# CurrentSensor.net
KiCad netlist of a schematic drawn in EAGLE
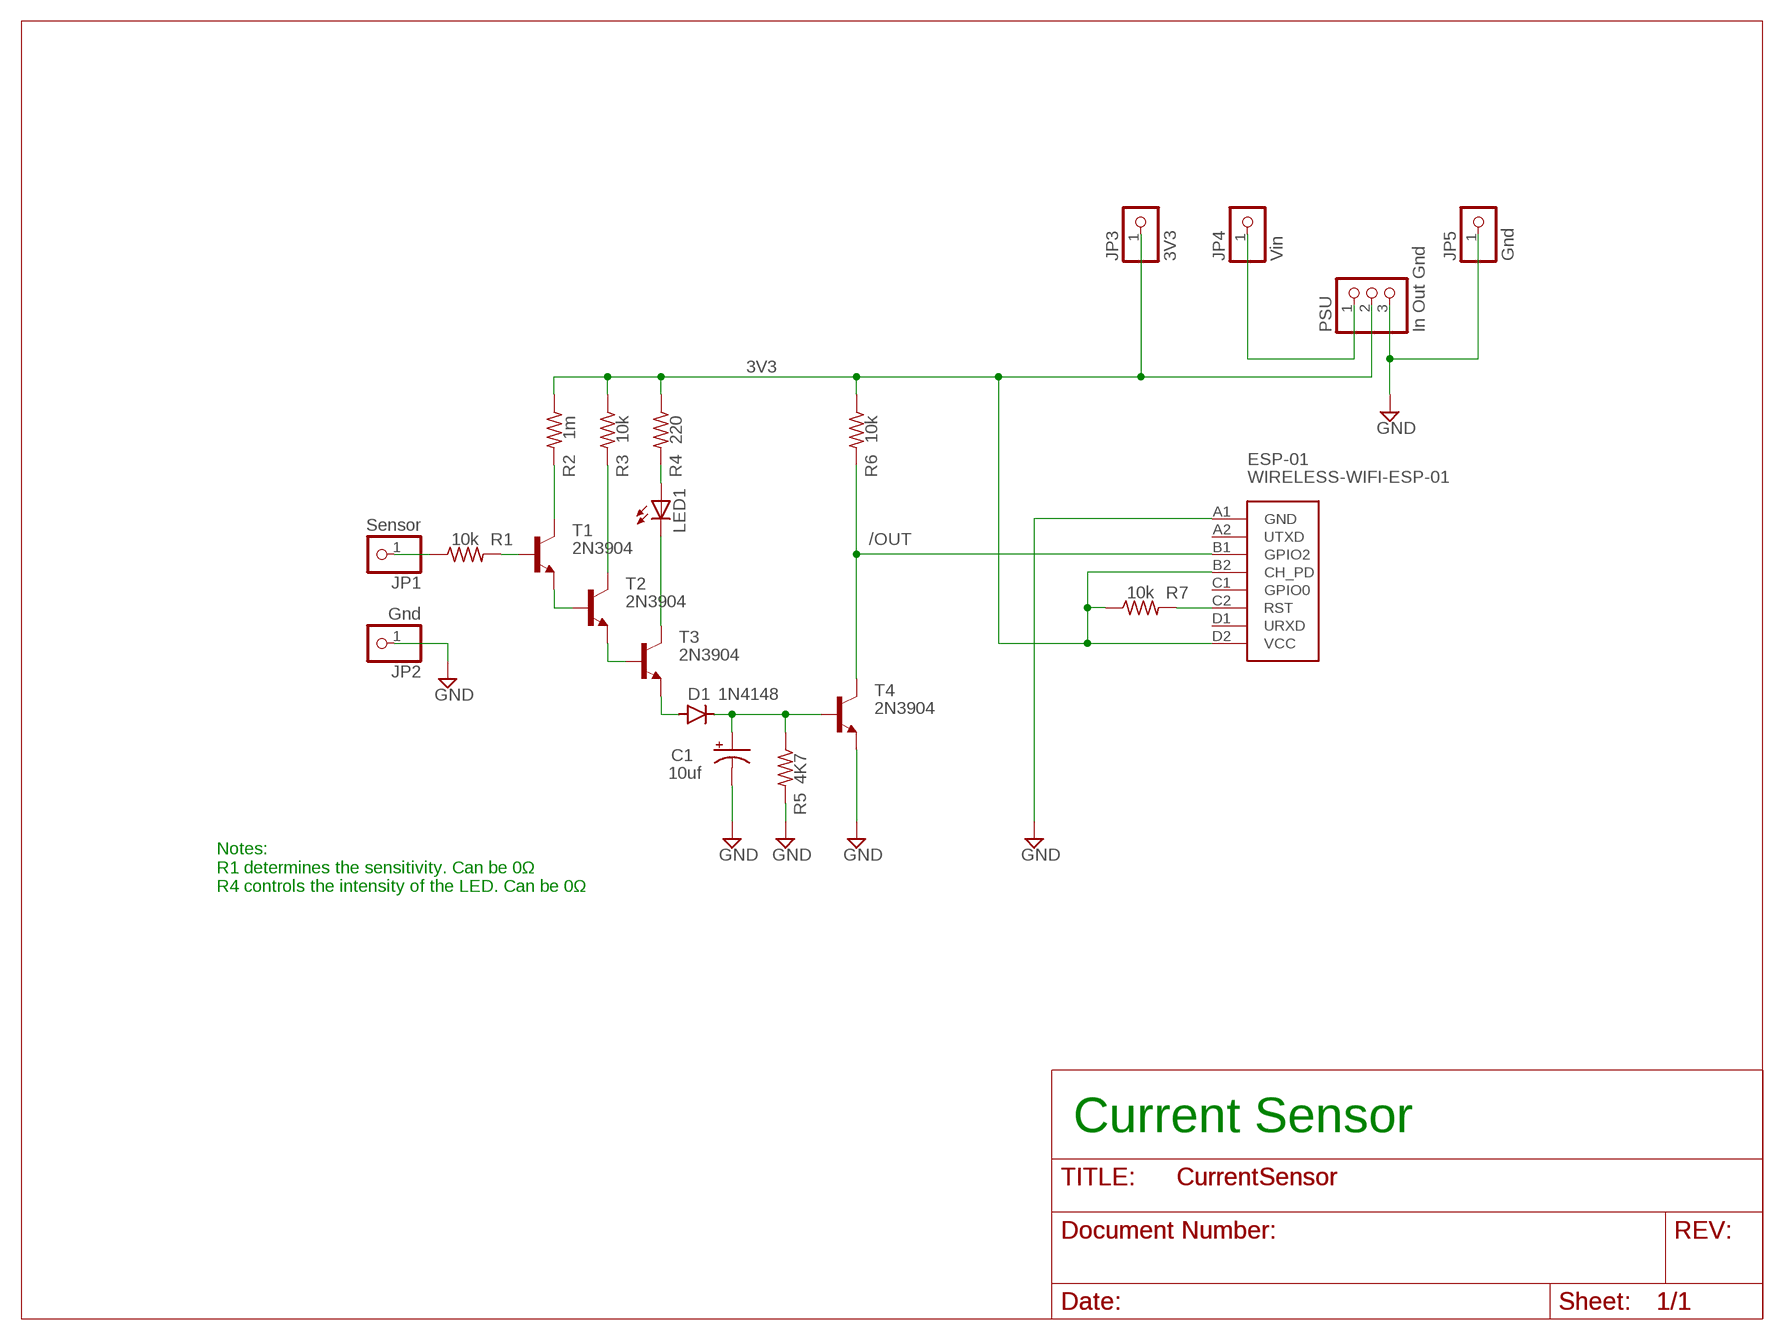
[diagram p0: schematic, sheet 1]

(export (version "E")
  (design (tool "Eeschema 10.0.6"))
  (components
    (comp (ref "C1")
      (value "10uf")
      (footprint "eagle-import:E15-5")
      (libsource (lib "eagle-import") (part "CPOL-USE15-5AXIAL"))
    )
    (comp (ref "D1")
      (value "1N4148")
      (footprint "eagle-import:DO35-10")
      (libsource (lib "eagle-import") (part "1N4148DO35-10"))
    )
    (comp (ref "ESP-01")
      (value "WIRELESS-WIFI-ESP-01")
      (footprint "eagle-import:WIRELESS-WIFI-ESP-01")
      (libsource (lib "eagle-import") (part "WIRELESS-WIFI-ESP-01"))
    )
    (comp (ref "JP1")
      (value "Sensor")
      (footprint "eagle-import:1X01")
      (libsource (lib "eagle-import") (part "adafruit_420_PINHD-1X1"))
    )
    (comp (ref "JP2")
      (value "Gnd")
      (footprint "eagle-import:1X01")
      (libsource (lib "eagle-import") (part "adafruit_420_PINHD-1X1"))
    )
    (comp (ref "JP3")
      (value "3V3")
      (footprint "eagle-import:1X01-CLEANBIG")
      (libsource (lib "eagle-import") (part "PINHD-1X1CB"))
    )
    (comp (ref "JP4")
      (value "Vin")
      (footprint "eagle-import:1X01-CLEANBIG")
      (libsource (lib "eagle-import") (part "PINHD-1X1CB"))
    )
    (comp (ref "JP5")
      (value "Gnd")
      (footprint "eagle-import:1X01-CLEANBIG")
      (libsource (lib "eagle-import") (part "PINHD-1X1CB"))
    )
    (comp (ref "LED1")
      (value "LED5MM")
      (footprint "eagle-import:LED5MM")
      (libsource (lib "eagle-import") (part "LED5MM"))
    )
    (comp (ref "PSU")
      (value "In Out Gnd")
      (footprint "eagle-import:1X03-CLEANBIG")
      (libsource (lib "eagle-import") (part "PINHD-1X3CB"))
    )
    (comp (ref "R1")
      (value "10k")
      (footprint "eagle-import:0207_9")
      (libsource (lib "eagle-import") (part "R-US_0207/9"))
    )
    (comp (ref "R2")
      (value "1m")
      (footprint "eagle-import:0207_9")
      (libsource (lib "eagle-import") (part "R-US_0207/9"))
    )
    (comp (ref "R3")
      (value "10k")
      (footprint "eagle-import:0207_9")
      (libsource (lib "eagle-import") (part "R-US_0207/9"))
    )
    (comp (ref "R4")
      (value "220")
      (footprint "eagle-import:0207_9")
      (libsource (lib "eagle-import") (part "R-US_0207/9"))
    )
    (comp (ref "R5")
      (value "4K7")
      (footprint "eagle-import:0207_9")
      (libsource (lib "eagle-import") (part "R-US_0207/9"))
    )
    (comp (ref "R6")
      (value "10k")
      (footprint "eagle-import:0207_9")
      (libsource (lib "eagle-import") (part "R-US_0207/9"))
    )
    (comp (ref "R7")
      (value "10k")
      (footprint "eagle-import:0207_9")
      (libsource (lib "eagle-import") (part "R-US_0207/9"))
    )
    (comp (ref "T1")
      (value "2N3904")
      (footprint "eagle-import:TO92")
      (libsource (lib "eagle-import") (part "2N3904"))
    )
    (comp (ref "T2")
      (value "2N3904")
      (footprint "eagle-import:TO92")
      (libsource (lib "eagle-import") (part "2N3904"))
    )
    (comp (ref "T3")
      (value "2N3904")
      (footprint "eagle-import:TO92")
      (libsource (lib "eagle-import") (part "2N3904"))
    )
    (comp (ref "T4")
      (value "2N3904")
      (footprint "eagle-import:TO92")
      (libsource (lib "eagle-import") (part "2N3904"))
    )
  )
  (nets
    (net (code "1") (name "/3V3") (class "Default")
      (node (ref "ESP-01") (pin "B2") (pinfunction "CH_PD_B2") (pintype "bidirectional"))
      (node (ref "ESP-01") (pin "D2") (pinfunction "VCC_D2") (pintype "power_in"))
      (node (ref "JP3") (pin "1") (pinfunction "1_1") (pintype "passive"))
      (node (ref "PSU") (pin "2") (pinfunction "2_2") (pintype "passive"))
      (node (ref "R2") (pin "1") (pinfunction "1_1") (pintype "passive"))
      (node (ref "R3") (pin "1") (pinfunction "1_1") (pintype "passive"))
      (node (ref "R4") (pin "1") (pinfunction "1_1") (pintype "passive"))
      (node (ref "R6") (pin "1") (pinfunction "1_1") (pintype "passive"))
      (node (ref "R7") (pin "1") (pinfunction "1_1") (pintype "passive"))
    )
    (net (code "2") (name "/{slash}OUT") (class "Default")
      (node (ref "ESP-01") (pin "B1") (pinfunction "GPIO2_B1") (pintype "bidirectional"))
      (node (ref "R6") (pin "2") (pinfunction "2_2") (pintype "passive"))
      (node (ref "T4") (pin "1") (pinfunction "C_1") (pintype "passive"))
    )
    (net (code "3") (name "GND") (class "Default")
      (node (ref "C1") (pin "-") (pinfunction "-_-") (pintype "passive"))
      (node (ref "ESP-01") (pin "A1") (pinfunction "GND_A1") (pintype "power_in"))
      (node (ref "JP2") (pin "1") (pinfunction "1_1") (pintype "passive"))
      (node (ref "JP5") (pin "1") (pinfunction "1_1") (pintype "passive"))
      (node (ref "PSU") (pin "3") (pinfunction "3_3") (pintype "passive"))
      (node (ref "R5") (pin "2") (pinfunction "2_2") (pintype "passive"))
      (node (ref "T4") (pin "3") (pinfunction "E_3") (pintype "passive"))
    )
    (net (code "4") (name "Net-(ESP-01-RST)") (class "Default")
      (node (ref "ESP-01") (pin "C2") (pinfunction "RST_C2") (pintype "bidirectional"))
      (node (ref "R7") (pin "2") (pinfunction "2_2") (pintype "passive"))
    )
    (net (code "5") (name "Net-(JP1-Pad1)") (class "Default")
      (node (ref "JP1") (pin "1") (pinfunction "1_1") (pintype "passive"))
      (node (ref "R1") (pin "1") (pinfunction "1_1") (pintype "passive"))
    )
    (net (code "6") (name "Net-(JP4-Pad1)") (class "Default")
      (node (ref "JP4") (pin "1") (pinfunction "1_1") (pintype "passive"))
      (node (ref "PSU") (pin "1") (pinfunction "1_1") (pintype "passive"))
    )
    (net (code "7") (name "Net-(LED1-C)") (class "Default")
      (node (ref "LED1") (pin "K") (pinfunction "C_K") (pintype "passive"))
      (node (ref "T3") (pin "1") (pinfunction "C_1") (pintype "passive"))
    )
    (net (code "8") (name "Net-(LED1-PadA)") (class "Default")
      (node (ref "LED1") (pin "A") (pinfunction "A_A") (pintype "passive"))
      (node (ref "R4") (pin "2") (pinfunction "2_2") (pintype "passive"))
    )
    (net (code "9") (name "Net-(T1-B)") (class "Default")
      (node (ref "R1") (pin "2") (pinfunction "2_2") (pintype "passive"))
      (node (ref "T1") (pin "2") (pinfunction "B_2") (pintype "passive"))
    )
    (net (code "10") (name "Net-(T1-C)") (class "Default")
      (node (ref "R2") (pin "2") (pinfunction "2_2") (pintype "passive"))
      (node (ref "T1") (pin "1") (pinfunction "C_1") (pintype "passive"))
    )
    (net (code "11") (name "Net-(T1-E)") (class "Default")
      (node (ref "T1") (pin "3") (pinfunction "E_3") (pintype "passive"))
      (node (ref "T2") (pin "2") (pinfunction "B_2") (pintype "passive"))
    )
    (net (code "12") (name "Net-(T2-C)") (class "Default")
      (node (ref "R3") (pin "2") (pinfunction "2_2") (pintype "passive"))
      (node (ref "T2") (pin "1") (pinfunction "C_1") (pintype "passive"))
    )
    (net (code "13") (name "Net-(T2-E)") (class "Default")
      (node (ref "T2") (pin "3") (pinfunction "E_3") (pintype "passive"))
      (node (ref "T3") (pin "2") (pinfunction "B_2") (pintype "passive"))
    )
    (net (code "14") (name "Net-(T3-E)") (class "Default")
      (node (ref "D1") (pin "A") (pinfunction "A_A") (pintype "passive"))
      (node (ref "T3") (pin "3") (pinfunction "E_3") (pintype "passive"))
    )
    (net (code "15") (name "Net-(T4-B)") (class "Default")
      (node (ref "C1") (pin "+") (pinfunction "+_+") (pintype "passive"))
      (node (ref "D1") (pin "C") (pinfunction "C_C") (pintype "passive"))
      (node (ref "R5") (pin "1") (pinfunction "1_1") (pintype "passive"))
      (node (ref "T4") (pin "2") (pinfunction "B_2") (pintype "passive"))
    )
    (net (code "16") (name "unconnected-(ESP-01-GPIO0-PadC1)") (class "Default")
      (node (ref "ESP-01") (pin "C1") (pinfunction "GPIO0_C1") (pintype "bidirectional"))
    )
    (net (code "17") (name "unconnected-(ESP-01-URXD-PadD1)") (class "Default")
      (node (ref "ESP-01") (pin "D1") (pinfunction "URXD_D1") (pintype "bidirectional"))
    )
    (net (code "18") (name "unconnected-(ESP-01-UTXD-PadA2)") (class "Default")
      (node (ref "ESP-01") (pin "A2") (pinfunction "UTXD_A2") (pintype "bidirectional"))
    )
  )
)
